# power.net
KiCad netlist of a schematic drawn in Altium Designer
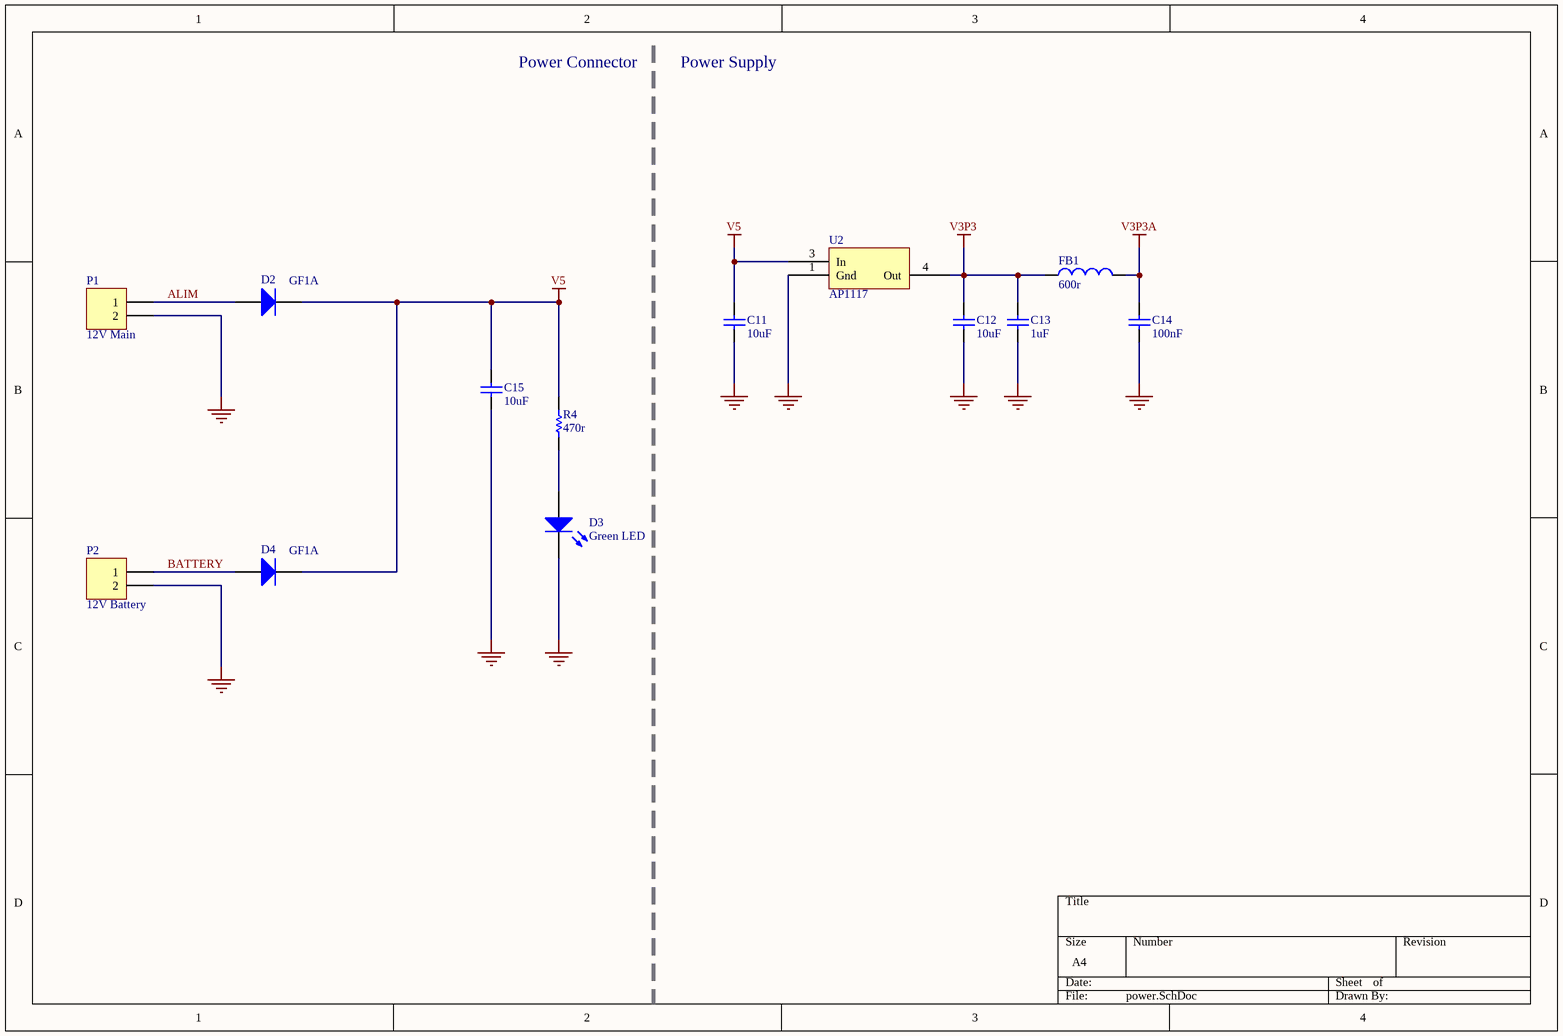
[diagram p0: power.SchDoc]

(export (version "E")
  (design (tool "Eeschema 10.0.6"))
  (components
    (comp (ref "C11")
      (value "10uF")
      (footprint "CAPC2012N")
      (description "Capacitor")
      (fields (field (name "PUBLISHER") "Altium Limited"))
      (libsource (lib "Miscellaneous Devices") (part "Cap"))
    )
    (comp (ref "C12")
      (value "10uF")
      (footprint "CAPC2012N")
      (description "Capacitor")
      (fields (field (name "PUBLISHER") "Altium Limited"))
      (libsource (lib "Miscellaneous Devices") (part "Cap"))
    )
    (comp (ref "C13")
      (value "1uF")
      (footprint "CAPC2012N")
      (description "Capacitor")
      (fields (field (name "PUBLISHER") "Altium Limited"))
      (libsource (lib "Miscellaneous Devices") (part "Cap"))
    )
    (comp (ref "C14")
      (value "100nF")
      (footprint "CAPC1608N")
      (description "Capacitor")
      (fields (field (name "PUBLISHER") "Altium Limited"))
      (libsource (lib "Miscellaneous Devices") (part "Cap"))
    )
    (comp (ref "C15")
      (value "10uF")
      (footprint "CAPC1608N")
      (description "Capacitor")
      (fields (field (name "PUBLISHER") "Altium Limited"))
      (libsource (lib "Miscellaneous Devices") (part "Cap"))
    )
    (comp (ref "D2")
      (value "GF1A")
      (footprint "SMA/DO-214AC_21")
      (description "Default Diode")
      (fields (field (name "PUBLISHER") "Altium Limited"))
      (libsource (lib "Miscellaneous Devices") (part "Diode"))
    )
    (comp (ref "D3")
      (value "Green LED")
      (footprint "LED 0805")
      (description "Typical INFRARED GaAs LED")
      (fields (field (name "PUBLISHER") "Altium Limited"))
      (libsource (lib "Miscellaneous Devices") (part "LED0"))
    )
    (comp (ref "D4")
      (value "GF1A")
      (footprint "SMA/DO-214AC_21")
      (description "Default Diode")
      (fields (field (name "PUBLISHER") "Altium Limited"))
      (libsource (lib "Miscellaneous Devices") (part "Diode"))
    )
    (comp (ref "FB1")
      (value "600r")
      (footprint "INDC1608AN")
      (description "Inductor")
      (fields (field (name "PUBLISHER") "Altium Limited"))
      (libsource (lib "Miscellaneous Devices") (part "Inductor"))
    )
    (comp (ref "P1")
      (value "12V Main")
      (footprint "PHOENIX_1985195")
      (description "Header, 2-Pin")
      (fields (field (name "PUBLISHER") "Altium Limited"))
      (libsource (lib "Miscellaneous Connectors") (part "Header 2"))
    )
    (comp (ref "P2")
      (value "12V Battery")
      (footprint "PHOENIX_1985195")
      (description "Header, 2-Pin")
      (fields (field (name "PUBLISHER") "Altium Limited"))
      (libsource (lib "Miscellaneous Connectors") (part "Header 2"))
    )
    (comp (ref "R4")
      (value "470r")
      (footprint "RESC1608N")
      (description "Resistor")
      (fields (field (name "PUBLISHER") "Altium Limited"))
      (libsource (lib "Miscellaneous Devices") (part "Res1"))
    )
    (comp (ref "U2") (value "AP1117") (footprint "TD03B_N") (libsource (lib "TP") (part "AP1117")))
  )
  (nets
    (net (code "1") (name "/ALIM") (class "Default")
      (node (ref "D2") (pin "1") (pinfunction "A_1") (pintype "passive"))
      (node (ref "P1") (pin "1") (pinfunction "1_1") (pintype "passive"))
    )
    (net (code "2") (name "/BATTERY") (class "Default")
      (node (ref "D4") (pin "1") (pinfunction "A_1") (pintype "passive"))
      (node (ref "P2") (pin "1") (pinfunction "1_1") (pintype "passive"))
    )
    (net (code "3") (name "GND") (class "Default")
      (node (ref "C11") (pin "1") (pinfunction "1_1") (pintype "passive"))
      (node (ref "C12") (pin "1") (pinfunction "1_1") (pintype "passive"))
      (node (ref "C13") (pin "1") (pinfunction "1_1") (pintype "passive"))
      (node (ref "C14") (pin "1") (pinfunction "1_1") (pintype "passive"))
      (node (ref "C15") (pin "1") (pinfunction "1_1") (pintype "passive"))
      (node (ref "D3") (pin "2") (pinfunction "K_2") (pintype "passive"))
      (node (ref "P1") (pin "2") (pinfunction "2_2") (pintype "passive"))
      (node (ref "P2") (pin "2") (pinfunction "2_2") (pintype "passive"))
      (node (ref "U2") (pin "1") (pinfunction "Gnd_1") (pintype "passive"))
    )
    (net (code "4") (name "Net-(D3-A)") (class "Default")
      (node (ref "D3") (pin "1") (pinfunction "A_1") (pintype "passive"))
      (node (ref "R4") (pin "1") (pinfunction "1_1") (pintype "passive"))
    )
    (net (code "5") (name "V3P3") (class "Default")
      (node (ref "C12") (pin "2") (pinfunction "2_2") (pintype "passive"))
      (node (ref "C13") (pin "2") (pinfunction "2_2") (pintype "passive"))
      (node (ref "FB1") (pin "1") (pinfunction "1_1") (pintype "passive"))
      (node (ref "U2") (pin "4") (pinfunction "Out_4") (pintype "passive"))
    )
    (net (code "6") (name "V3P3A") (class "Default")
      (node (ref "C14") (pin "2") (pinfunction "2_2") (pintype "passive"))
      (node (ref "FB1") (pin "2") (pinfunction "2_2") (pintype "passive"))
    )
    (net (code "7") (name "V5") (class "Default")
      (node (ref "C11") (pin "2") (pinfunction "2_2") (pintype "passive"))
      (node (ref "C15") (pin "2") (pinfunction "2_2") (pintype "passive"))
      (node (ref "D2") (pin "2") (pinfunction "K_2") (pintype "passive"))
      (node (ref "D4") (pin "2") (pinfunction "K_2") (pintype "passive"))
      (node (ref "R4") (pin "2") (pinfunction "2_2") (pintype "passive"))
      (node (ref "U2") (pin "3") (pinfunction "In_3") (pintype "passive"))
    )
  )
)
